# pic.net
KiCad netlist of a schematic drawn in Altium Designer
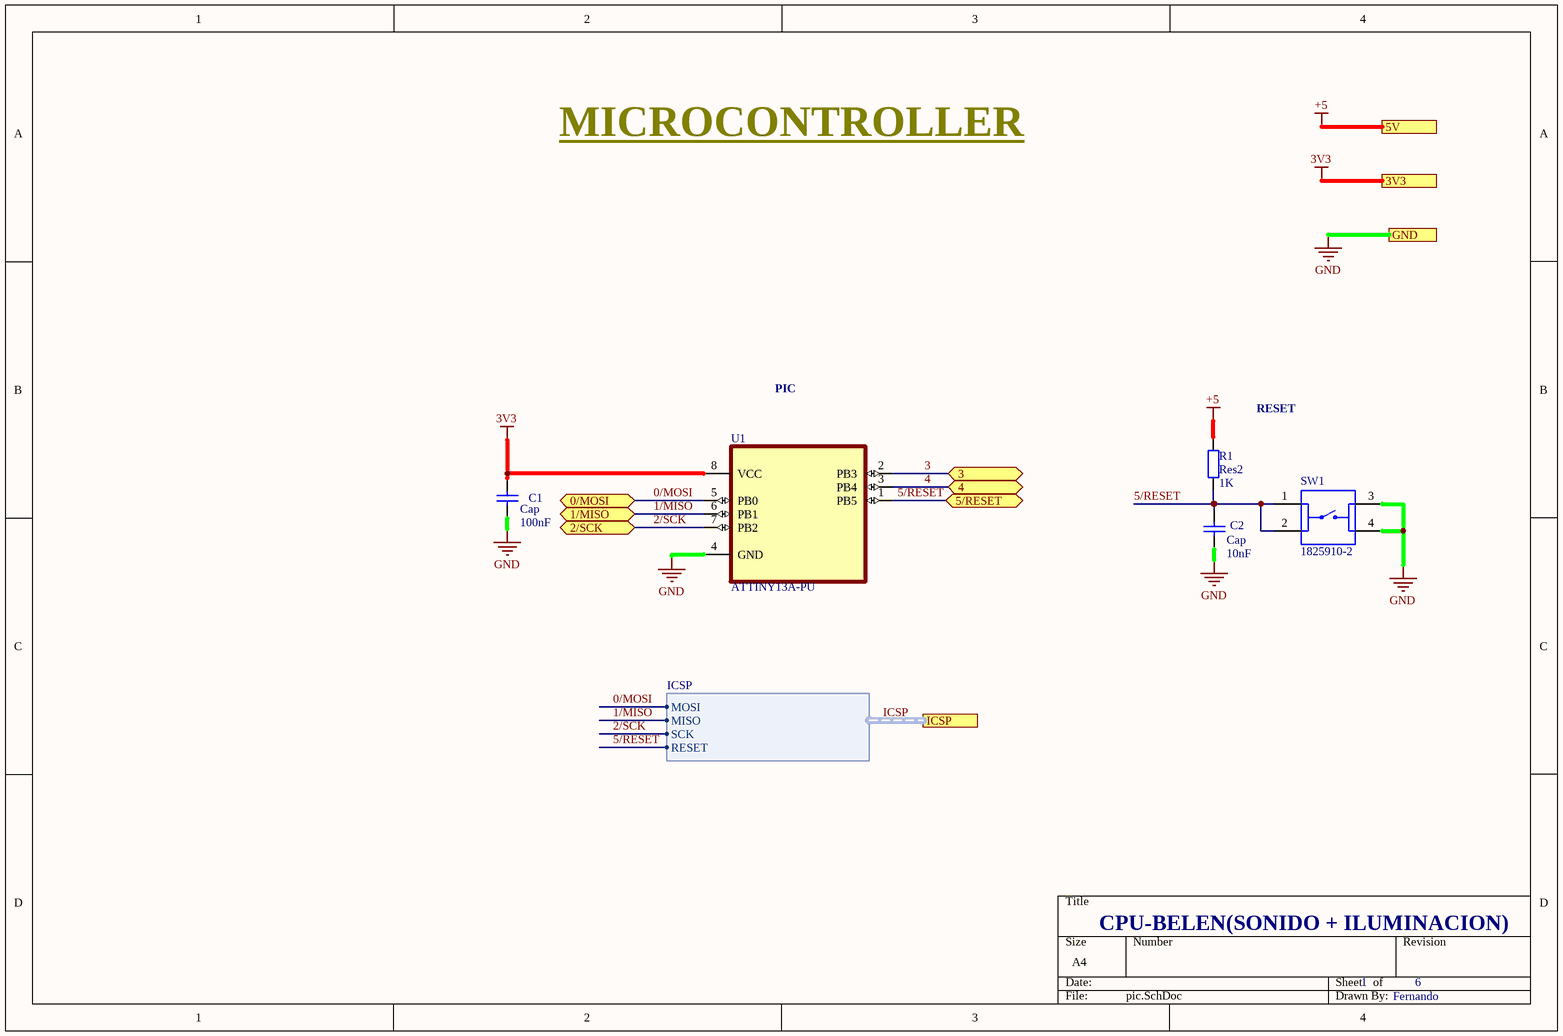
[diagram p0: pic.SchDoc]

(export (version "E")
  (design (tool "Eeschema 10.0.6"))
  (components
    (comp (ref "C1")
      (value "Cap")
      (footprint "RAD-0.3")
      (description "Capacitor")
      (fields (field (name "ALTIUM_VALUE") "100nF") (field (name "PUBLISHER") "Altium Limited"))
      (libsource (lib "Miscellaneous Devices") (part "Cap"))
    )
    (comp (ref "C2")
      (value "Cap")
      (footprint "RAD-0.3")
      (description "Capacitor")
      (fields (field (name "ALTIUM_VALUE") "10nF") (field (name "PUBLISHER") "Altium Limited"))
      (libsource (lib "Miscellaneous Devices") (part "Cap"))
    )
    (comp (ref "R1")
      (value "Res2")
      (footprint "AXIAL-0.4")
      (description "Resistor")
      (fields (field (name "ALTIUM_VALUE") "1K") (field (name "PUBLISHER") "Altium Limited"))
      (libsource (lib "Miscellaneous Devices") (part "Res2"))
    )
    (comp (ref "SW1")
      (value "1825910-2")
      (footprint "TE_1825910-2")
      (description "50 mA SPST Round Actuator 160 Gram Force Tactile Pushbutton Switch")
      (fields (field (name "MF") "TE Connectivity"))
      (libsource (lib "1825910-2") (part "1825910-2"))
    )
    (comp (ref "U1")
      (value "ATTINY13A-PU")
      (footprint "DIP254P762X533-8")
      (description "AVR AVRÂ® ATtiny Microcontroller IC 8-Bit 20MHz 1KB _512 x 16_ FLASH 8-PDIP")
      (fields (field (name "MF") "Microchip"))
      (libsource (lib "ATTINY13A-PU (1)") (part "ATTINY13A-PU"))
    )
  )
  (nets
    (net (code "2") (name "+5") (class "Default")
      (node (ref "R1") (pin "2") (pinfunction "2_2") (pintype "passive"))
    )
    (net (code "3") (name "/0{slash}MOSI") (class "Default")
      (node (ref "U1") (pin "5") (pinfunction "PB0_5") (pintype "bidirectional"))
    )
    (net (code "4") (name "/1{slash}MISO") (class "Default")
      (node (ref "U1") (pin "6") (pinfunction "PB1_6") (pintype "bidirectional"))
    )
    (net (code "5") (name "/2{slash}SCK") (class "Default")
      (node (ref "U1") (pin "7") (pinfunction "PB2_7") (pintype "bidirectional"))
    )
    (net (code "6") (name "/3") (class "Default")
      (node (ref "U1") (pin "2") (pinfunction "PB3_2") (pintype "bidirectional"))
    )
    (net (code "7") (name "/4") (class "Default")
      (node (ref "U1") (pin "3") (pinfunction "PB4_3") (pintype "bidirectional"))
    )
    (net (code "8") (name "/5{slash}RESET") (class "Default")
      (node (ref "C2") (pin "2") (pinfunction "2_2") (pintype "passive"))
      (node (ref "R1") (pin "1") (pinfunction "1_1") (pintype "passive"))
      (node (ref "SW1") (pin "1") (pinfunction "1_1") (pintype "passive"))
      (node (ref "SW1") (pin "2") (pinfunction "2_2") (pintype "passive"))
      (node (ref "U1") (pin "1") (pinfunction "PB5_1") (pintype "bidirectional"))
    )
    (net (code "10") (name "3V3") (class "Default")
      (node (ref "C1") (pin "2") (pinfunction "2_2") (pintype "passive"))
      (node (ref "U1") (pin "8") (pinfunction "VCC_8") (pintype "power_in"))
    )
    (net (code "11") (name "GND") (class "Default")
      (node (ref "C1") (pin "1") (pinfunction "1_1") (pintype "passive"))
      (node (ref "C2") (pin "1") (pinfunction "1_1") (pintype "passive"))
      (node (ref "SW1") (pin "3") (pinfunction "3_3") (pintype "passive"))
      (node (ref "SW1") (pin "4") (pinfunction "4_4") (pintype "passive"))
      (node (ref "U1") (pin "4") (pinfunction "GND_4") (pintype "passive"))
    )
  )
)
